# ControlBoardV1.net
KiCad netlist of a schematic drawn in EAGLE
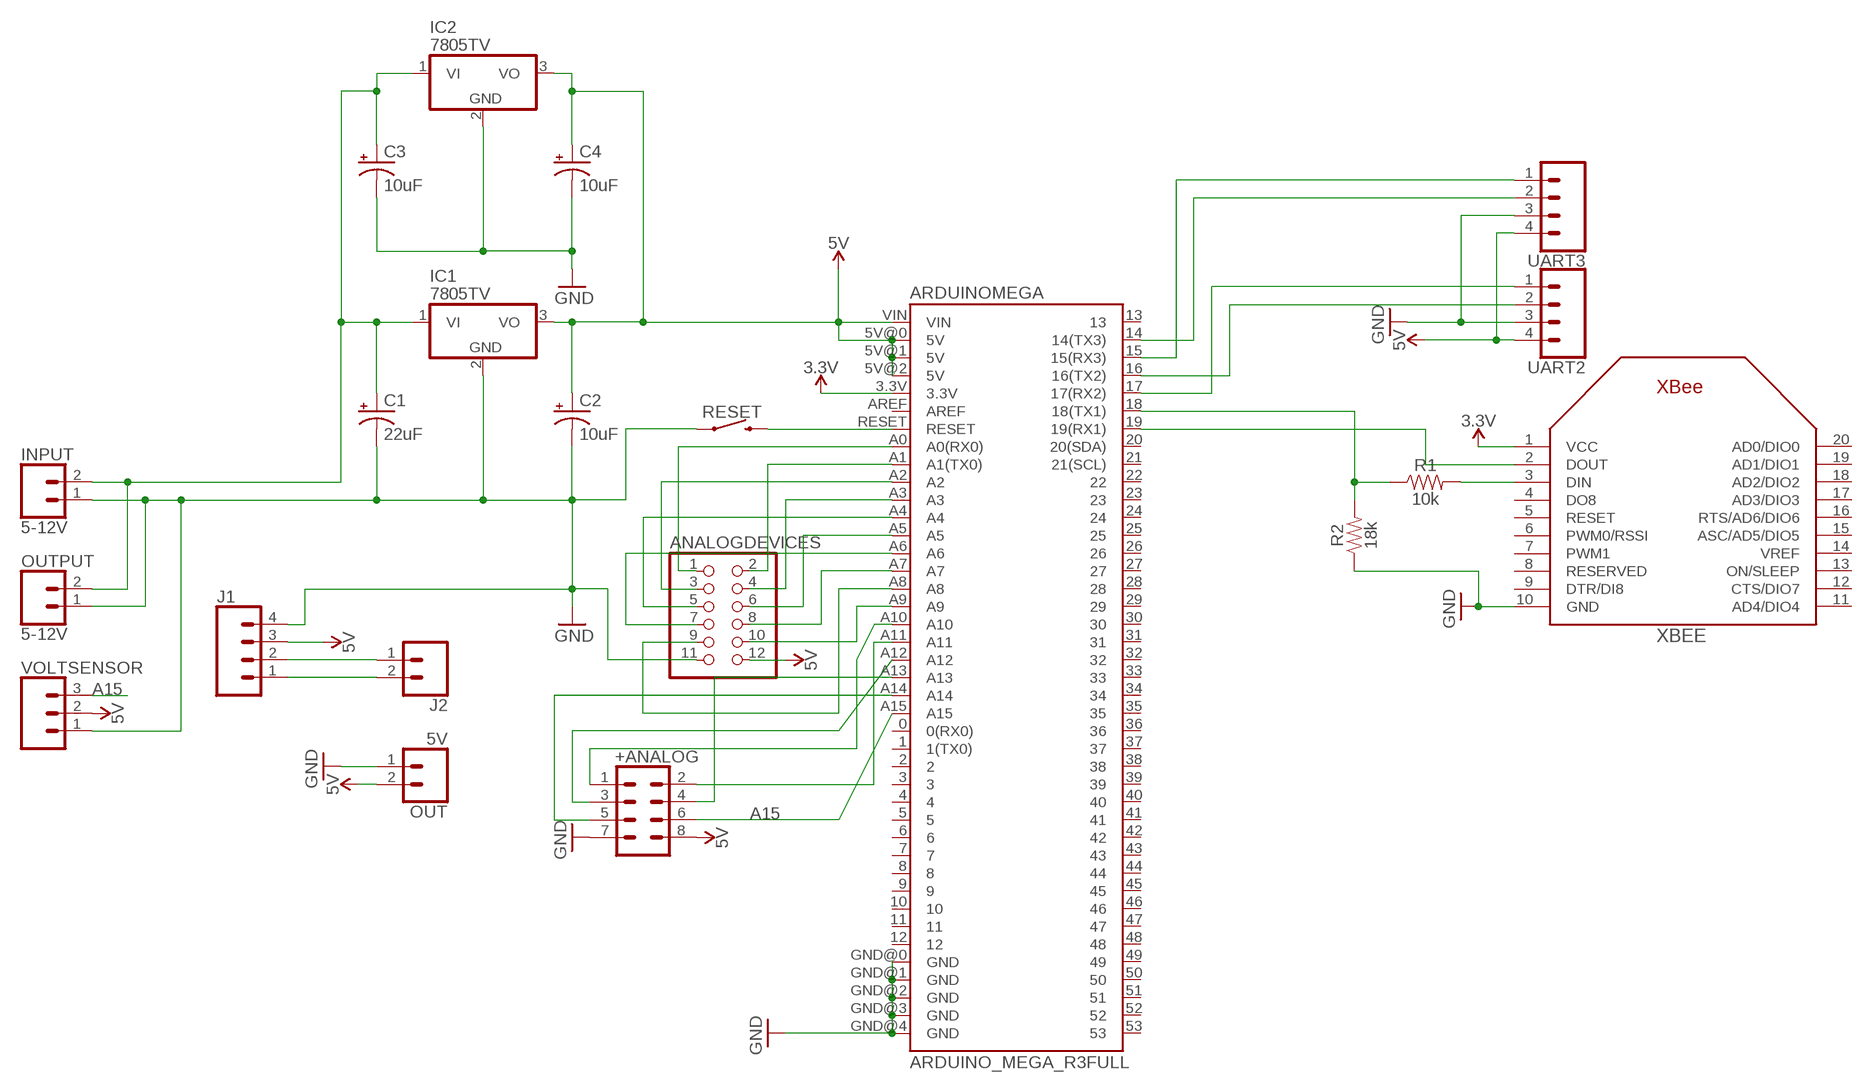
[diagram p0: schematic, sheet 1]

(export (version "E")
  (design (tool "Eeschema 10.0.6"))
  (components
    (comp (ref "+ANALOG")
      (value "CONN_04X2")
      (footprint "eagle-import:2X4")
      (libsource (lib "eagle-import") (part "CONN_04X2"))
    )
    (comp (ref "ANALOGDEVICES")
      (value "PINHD-2X6")
      (footprint "eagle-import:2X06")
      (libsource (lib "eagle-import") (part "PINHD-2X6"))
    )
    (comp (ref "ARDUINOMEGA")
      (value "ARDUINO_MEGA_R3FULL")
      (footprint "eagle-import:ARDUINO_MEGA")
      (libsource (lib "eagle-import") (part "ARDUINO_MEGA_R3FULL"))
    )
    (comp (ref "C1")
      (value "22uF")
      (footprint "eagle-import:E2,5-5")
      (libsource (lib "eagle-import") (part "CPOL-USE2.5-5"))
    )
    (comp (ref "C2")
      (value "10uF")
      (footprint "eagle-import:E2,5-5")
      (libsource (lib "eagle-import") (part "CPOL-USE2.5-5"))
    )
    (comp (ref "C3")
      (value "10uF")
      (footprint "eagle-import:E2,5-5")
      (libsource (lib "eagle-import") (part "CPOL-USE2.5-5"))
    )
    (comp (ref "C4")
      (value "10uF")
      (footprint "eagle-import:E2,5-5")
      (libsource (lib "eagle-import") (part "CPOL-USE2.5-5"))
    )
    (comp (ref "IC1")
      (value "7805TV")
      (footprint "eagle-import:TO220V")
      (libsource (lib "eagle-import") (part "78TV05"))
    )
    (comp (ref "IC2")
      (value "7805TV")
      (footprint "eagle-import:TO220V")
      (libsource (lib "eagle-import") (part "78TV05"))
    )
    (comp (ref "INPUT")
      (value "5-12V")
      (footprint "eagle-import:SCREWTERMINAL-3.5MM-2")
      (libsource (lib "eagle-import") (part "CONN_023.5MM"))
    )
    (comp (ref "J1")
      (value "CONN_04")
      (footprint "eagle-import:1X04")
      (libsource (lib "eagle-import") (part "CONN_04"))
    )
    (comp (ref "J2")
      (value "CONN_02")
      (footprint "eagle-import:1X02")
      (libsource (lib "eagle-import") (part "CONN_02"))
    )
    (comp (ref "OUT")
      (value "5V")
      (footprint "eagle-import:SCREWTERMINAL-3.5MM-2")
      (libsource (lib "eagle-import") (part "CONN_023.5MM"))
    )
    (comp (ref "OUTPUT")
      (value "5-12V")
      (footprint "eagle-import:SCREWTERMINAL-3.5MM-2")
      (libsource (lib "eagle-import") (part "CONN_023.5MM"))
    )
    (comp (ref "R1")
      (value "10k")
      (footprint "eagle-import:AXIAL-0.3")
      (libsource (lib "eagle-import") (part "10KOHM-HORIZ-1/4W-1%"))
    )
    (comp (ref "R2")
      (value "18k")
      (footprint "eagle-import:AXIAL-0.3")
      (libsource (lib "eagle-import") (part "10KOHM-HORIZ-1/4W-1%"))
    )
    (comp (ref "RESET")
      (value "MOMENTARY-SWITCH-SPST-PTH-6.0MM")
      (footprint "eagle-import:TACTILE_SWITCH_PTH_6.0MM")
      (libsource (lib "eagle-import") (part "MOMENTARY-SWITCH-SPST-PTH-6.0MM"))
    )
    (comp (ref "UART2")
      (value "CONN_04")
      (footprint "eagle-import:1X04")
      (libsource (lib "eagle-import") (part "CONN_04"))
    )
    (comp (ref "UART3")
      (value "CONN_04")
      (footprint "eagle-import:1X04")
      (libsource (lib "eagle-import") (part "CONN_04"))
    )
    (comp (ref "VOLTSENSOR")
      (value "CONN_03")
      (footprint "eagle-import:1X03")
      (libsource (lib "eagle-import") (part "CONN_03"))
    )
    (comp (ref "XBEE")
      (value "XBEE")
      (footprint "eagle-import:XBEE")
      (libsource (lib "eagle-import") (part "XBEE"))
    )
  )
  (nets
    (net (code "1") (name "/A15") (class "Default")
      (node (ref "+ANALOG") (pin "6") (pinfunction "6_6") (pintype "passive"))
      (node (ref "ARDUINOMEGA") (pin "A15") (pinfunction "A15_A15") (pintype "bidirectional"))
      (node (ref "VOLTSENSOR") (pin "3") (pinfunction "3_3") (pintype "passive"))
    )
    (net (code "2") (name "3.3V") (class "Default")
      (node (ref "ARDUINOMEGA") (pin "3.3V") (pinfunction "3.3V_3.3V") (pintype "bidirectional"))
      (node (ref "XBEE") (pin "1") (pinfunction "VCC_1") (pintype "power_in"))
    )
    (net (code "3") (name "5V") (class "Default")
      (node (ref "+ANALOG") (pin "8") (pinfunction "8_8") (pintype "passive"))
      (node (ref "ANALOGDEVICES") (pin "12") (pinfunction "12_12") (pintype "passive"))
      (node (ref "ARDUINOMEGA") (pin "5V@0") (pinfunction "5V_5V@0") (pintype "bidirectional"))
      (node (ref "ARDUINOMEGA") (pin "5V@1") (pinfunction "5V_5V@1") (pintype "bidirectional"))
      (node (ref "ARDUINOMEGA") (pin "5V@2") (pinfunction "5V_5V@2") (pintype "bidirectional"))
      (node (ref "ARDUINOMEGA") (pin "VIN") (pinfunction "VIN_VIN") (pintype "bidirectional"))
      (node (ref "C2") (pin "+") (pinfunction "+_+") (pintype "passive"))
      (node (ref "C4") (pin "+") (pinfunction "+_+") (pintype "passive"))
      (node (ref "IC1") (pin "3") (pinfunction "VO_3") (pintype "passive"))
      (node (ref "IC2") (pin "3") (pinfunction "VO_3") (pintype "passive"))
      (node (ref "J1") (pin "3") (pinfunction "3_3") (pintype "passive"))
      (node (ref "OUT") (pin "2") (pinfunction "2_2") (pintype "passive"))
      (node (ref "UART2") (pin "4") (pinfunction "4_4") (pintype "passive"))
      (node (ref "UART3") (pin "4") (pinfunction "4_4") (pintype "passive"))
      (node (ref "VOLTSENSOR") (pin "2") (pinfunction "2_2") (pintype "passive"))
    )
    (net (code "4") (name "GND") (class "Default")
      (node (ref "+ANALOG") (pin "7") (pinfunction "7_7") (pintype "passive"))
      (node (ref "ANALOGDEVICES") (pin "11") (pinfunction "11_11") (pintype "passive"))
      (node (ref "ARDUINOMEGA") (pin "GND@0") (pinfunction "GND_GND@0") (pintype "bidirectional"))
      (node (ref "ARDUINOMEGA") (pin "GND@1") (pinfunction "GND_GND@1") (pintype "bidirectional"))
      (node (ref "ARDUINOMEGA") (pin "GND@2") (pinfunction "GND_GND@2") (pintype "bidirectional"))
      (node (ref "ARDUINOMEGA") (pin "GND@3") (pinfunction "GND_GND@3") (pintype "bidirectional"))
      (node (ref "ARDUINOMEGA") (pin "GND@4") (pinfunction "GND_GND@4") (pintype "bidirectional"))
      (node (ref "C1") (pin "-") (pinfunction "-_-") (pintype "passive"))
      (node (ref "C2") (pin "-") (pinfunction "-_-") (pintype "passive"))
      (node (ref "C3") (pin "-") (pinfunction "-_-") (pintype "passive"))
      (node (ref "C4") (pin "-") (pinfunction "-_-") (pintype "passive"))
      (node (ref "IC1") (pin "2") (pinfunction "GND_2") (pintype "passive"))
      (node (ref "IC2") (pin "2") (pinfunction "GND_2") (pintype "passive"))
      (node (ref "INPUT") (pin "1") (pinfunction "1_1") (pintype "passive"))
      (node (ref "J1") (pin "4") (pinfunction "4_4") (pintype "passive"))
      (node (ref "OUT") (pin "1") (pinfunction "1_1") (pintype "passive"))
      (node (ref "OUTPUT") (pin "1") (pinfunction "1_1") (pintype "passive"))
      (node (ref "R2") (pin "P$1") (pinfunction "1_P$1") (pintype "passive"))
      (node (ref "RESET") (pin "1") (pinfunction "1_1") (pintype "passive"))
      (node (ref "UART2") (pin "3") (pinfunction "3_3") (pintype "passive"))
      (node (ref "UART3") (pin "3") (pinfunction "3_3") (pintype "passive"))
      (node (ref "VOLTSENSOR") (pin "1") (pinfunction "1_1") (pintype "passive"))
      (node (ref "XBEE") (pin "10") (pinfunction "GND_10") (pintype "power_in"))
    )
    (net (code "5") (name "Net-(+ANALOG-Pad1)") (class "Default")
      (node (ref "+ANALOG") (pin "1") (pinfunction "1_1") (pintype "passive"))
      (node (ref "ARDUINOMEGA") (pin "A10") (pinfunction "A10_A10") (pintype "bidirectional"))
    )
    (net (code "6") (name "Net-(+ANALOG-Pad2)") (class "Default")
      (node (ref "+ANALOG") (pin "2") (pinfunction "2_2") (pintype "passive"))
      (node (ref "ARDUINOMEGA") (pin "A11") (pinfunction "A11_A11") (pintype "bidirectional"))
    )
    (net (code "7") (name "Net-(+ANALOG-Pad3)") (class "Default")
      (node (ref "+ANALOG") (pin "3") (pinfunction "3_3") (pintype "passive"))
      (node (ref "ARDUINOMEGA") (pin "A12") (pinfunction "A12_A12") (pintype "bidirectional"))
    )
    (net (code "8") (name "Net-(+ANALOG-Pad4)") (class "Default")
      (node (ref "+ANALOG") (pin "4") (pinfunction "4_4") (pintype "passive"))
      (node (ref "ARDUINOMEGA") (pin "A13") (pinfunction "A13_A13") (pintype "bidirectional"))
    )
    (net (code "9") (name "Net-(+ANALOG-Pad5)") (class "Default")
      (node (ref "+ANALOG") (pin "5") (pinfunction "5_5") (pintype "passive"))
      (node (ref "ARDUINOMEGA") (pin "A14") (pinfunction "A14_A14") (pintype "bidirectional"))
    )
    (net (code "10") (name "Net-(ANALOGDEVICES-Pad3)") (class "Default")
      (node (ref "ANALOGDEVICES") (pin "3") (pinfunction "3_3") (pintype "passive"))
      (node (ref "ARDUINOMEGA") (pin "A2") (pinfunction "A2_A2") (pintype "bidirectional"))
    )
    (net (code "11") (name "Net-(ANALOGDEVICES-Pad4)") (class "Default")
      (node (ref "ANALOGDEVICES") (pin "4") (pinfunction "4_4") (pintype "passive"))
      (node (ref "ARDUINOMEGA") (pin "A3") (pinfunction "A3_A3") (pintype "bidirectional"))
    )
    (net (code "12") (name "Net-(ANALOGDEVICES-Pad5)") (class "Default")
      (node (ref "ANALOGDEVICES") (pin "5") (pinfunction "5_5") (pintype "passive"))
      (node (ref "ARDUINOMEGA") (pin "A4") (pinfunction "A4_A4") (pintype "bidirectional"))
    )
    (net (code "13") (name "Net-(ANALOGDEVICES-Pad6)") (class "Default")
      (node (ref "ANALOGDEVICES") (pin "6") (pinfunction "6_6") (pintype "passive"))
      (node (ref "ARDUINOMEGA") (pin "A5") (pinfunction "A5_A5") (pintype "bidirectional"))
    )
    (net (code "14") (name "Net-(ANALOGDEVICES-Pad7)") (class "Default")
      (node (ref "ANALOGDEVICES") (pin "7") (pinfunction "7_7") (pintype "passive"))
      (node (ref "ARDUINOMEGA") (pin "A6") (pinfunction "A6_A6") (pintype "bidirectional"))
    )
    (net (code "15") (name "Net-(ANALOGDEVICES-Pad8)") (class "Default")
      (node (ref "ANALOGDEVICES") (pin "8") (pinfunction "8_8") (pintype "passive"))
      (node (ref "ARDUINOMEGA") (pin "A7") (pinfunction "A7_A7") (pintype "bidirectional"))
    )
    (net (code "16") (name "Net-(ANALOGDEVICES-Pad9)") (class "Default")
      (node (ref "ANALOGDEVICES") (pin "9") (pinfunction "9_9") (pintype "passive"))
      (node (ref "ARDUINOMEGA") (pin "A8") (pinfunction "A8_A8") (pintype "bidirectional"))
    )
    (net (code "17") (name "Net-(ANALOGDEVICES-Pad10)") (class "Default")
      (node (ref "ANALOGDEVICES") (pin "10") (pinfunction "10_10") (pintype "passive"))
      (node (ref "ARDUINOMEGA") (pin "A9") (pinfunction "A9_A9") (pintype "bidirectional"))
    )
    (net (code "18") (name "Net-(ARDUINOMEGA-14(TX3))") (class "Default")
      (node (ref "ARDUINOMEGA") (pin "14") (pinfunction "14(TX3)_14") (pintype "bidirectional"))
      (node (ref "UART3") (pin "2") (pinfunction "2_2") (pintype "passive"))
    )
    (net (code "19") (name "Net-(ARDUINOMEGA-15(RX3))") (class "Default")
      (node (ref "ARDUINOMEGA") (pin "15") (pinfunction "15(RX3)_15") (pintype "bidirectional"))
      (node (ref "UART3") (pin "1") (pinfunction "1_1") (pintype "passive"))
    )
    (net (code "20") (name "Net-(ARDUINOMEGA-16(TX2))") (class "Default")
      (node (ref "ARDUINOMEGA") (pin "16") (pinfunction "16(TX2)_16") (pintype "bidirectional"))
      (node (ref "UART2") (pin "2") (pinfunction "2_2") (pintype "passive"))
    )
    (net (code "21") (name "Net-(ARDUINOMEGA-17(RX2))") (class "Default")
      (node (ref "ARDUINOMEGA") (pin "17") (pinfunction "17(RX2)_17") (pintype "bidirectional"))
      (node (ref "UART2") (pin "1") (pinfunction "1_1") (pintype "passive"))
    )
    (net (code "22") (name "Net-(ARDUINOMEGA-18(TX1))") (class "Default")
      (node (ref "ARDUINOMEGA") (pin "18") (pinfunction "18(TX1)_18") (pintype "bidirectional"))
      (node (ref "R1") (pin "P$1") (pinfunction "1_P$1") (pintype "passive"))
      (node (ref "R2") (pin "P$2") (pinfunction "2_P$2") (pintype "passive"))
    )
    (net (code "23") (name "Net-(ARDUINOMEGA-19(RX1))") (class "Default")
      (node (ref "ARDUINOMEGA") (pin "19") (pinfunction "19(RX1)_19") (pintype "bidirectional"))
      (node (ref "XBEE") (pin "2") (pinfunction "DOUT_2") (pintype "output"))
    )
    (net (code "24") (name "Net-(ARDUINOMEGA-A0(RX0))") (class "Default")
      (node (ref "ANALOGDEVICES") (pin "1") (pinfunction "1_1") (pintype "passive"))
      (node (ref "ARDUINOMEGA") (pin "A0") (pinfunction "A0(RX0)_A0") (pintype "bidirectional"))
    )
    (net (code "25") (name "Net-(ARDUINOMEGA-A1(TX0))") (class "Default")
      (node (ref "ANALOGDEVICES") (pin "2") (pinfunction "2_2") (pintype "passive"))
      (node (ref "ARDUINOMEGA") (pin "A1") (pinfunction "A1(TX0)_A1") (pintype "bidirectional"))
    )
    (net (code "26") (name "Net-(IC1-VI)") (class "Default")
      (node (ref "C1") (pin "+") (pinfunction "+_+") (pintype "passive"))
      (node (ref "C3") (pin "+") (pinfunction "+_+") (pintype "passive"))
      (node (ref "IC1") (pin "1") (pinfunction "VI_1") (pintype "input"))
      (node (ref "IC2") (pin "1") (pinfunction "VI_1") (pintype "input"))
      (node (ref "INPUT") (pin "2") (pinfunction "2_2") (pintype "passive"))
      (node (ref "OUTPUT") (pin "2") (pinfunction "2_2") (pintype "passive"))
    )
    (net (code "27") (name "Net-(J1-Pad1)") (class "Default")
      (node (ref "J1") (pin "1") (pinfunction "1_1") (pintype "passive"))
      (node (ref "J2") (pin "2") (pinfunction "2_2") (pintype "passive"))
    )
    (net (code "28") (name "Net-(J1-Pad2)") (class "Default")
      (node (ref "J1") (pin "2") (pinfunction "2_2") (pintype "passive"))
      (node (ref "J2") (pin "1") (pinfunction "1_1") (pintype "passive"))
    )
    (net (code "29") (name "Net-(R1-2)") (class "Default")
      (node (ref "R1") (pin "P$2") (pinfunction "2_P$2") (pintype "passive"))
      (node (ref "XBEE") (pin "3") (pinfunction "DIN_3") (pintype "input"))
    )
    (net (code "30") (name "Net-(RESET-2)") (class "Default")
      (node (ref "ARDUINOMEGA") (pin "RESET") (pinfunction "RESET_RESET") (pintype "bidirectional"))
      (node (ref "RESET") (pin "3") (pinfunction "2_3") (pintype "passive"))
    )
    (net (code "31") (name "unconnected-(ARDUINOMEGA-0(RX0)-Pad0)") (class "Default")
      (node (ref "ARDUINOMEGA") (pin "0") (pinfunction "0(RX0)_0") (pintype "bidirectional"))
    )
    (net (code "32") (name "unconnected-(ARDUINOMEGA-1(TX0)-Pad1)") (class "Default")
      (node (ref "ARDUINOMEGA") (pin "1") (pinfunction "1(TX0)_1") (pintype "bidirectional"))
    )
    (net (code "33") (name "unconnected-(ARDUINOMEGA-20(SDA)-Pad20)") (class "Default")
      (node (ref "ARDUINOMEGA") (pin "20") (pinfunction "20(SDA)_20") (pintype "bidirectional"))
    )
    (net (code "34") (name "unconnected-(ARDUINOMEGA-21(SCL)-Pad21)") (class "Default")
      (node (ref "ARDUINOMEGA") (pin "21") (pinfunction "21(SCL)_21") (pintype "bidirectional"))
    )
    (net (code "35") (name "unconnected-(ARDUINOMEGA-Pad2)") (class "Default")
      (node (ref "ARDUINOMEGA") (pin "2") (pinfunction "2_2") (pintype "bidirectional"))
    )
    (net (code "36") (name "unconnected-(ARDUINOMEGA-Pad3)") (class "Default")
      (node (ref "ARDUINOMEGA") (pin "3") (pinfunction "3_3") (pintype "bidirectional"))
    )
    (net (code "37") (name "unconnected-(ARDUINOMEGA-Pad4)") (class "Default")
      (node (ref "ARDUINOMEGA") (pin "4") (pinfunction "4_4") (pintype "bidirectional"))
    )
    (net (code "38") (name "unconnected-(ARDUINOMEGA-Pad5)") (class "Default")
      (node (ref "ARDUINOMEGA") (pin "5") (pinfunction "5_5") (pintype "bidirectional"))
    )
    (net (code "39") (name "unconnected-(ARDUINOMEGA-Pad6)") (class "Default")
      (node (ref "ARDUINOMEGA") (pin "6") (pinfunction "6_6") (pintype "bidirectional"))
    )
    (net (code "40") (name "unconnected-(ARDUINOMEGA-Pad7)") (class "Default")
      (node (ref "ARDUINOMEGA") (pin "7") (pinfunction "7_7") (pintype "bidirectional"))
    )
    (net (code "41") (name "unconnected-(ARDUINOMEGA-Pad8)") (class "Default")
      (node (ref "ARDUINOMEGA") (pin "8") (pinfunction "8_8") (pintype "bidirectional"))
    )
    (net (code "42") (name "unconnected-(ARDUINOMEGA-Pad9)") (class "Default")
      (node (ref "ARDUINOMEGA") (pin "9") (pinfunction "9_9") (pintype "bidirectional"))
    )
    (net (code "43") (name "unconnected-(ARDUINOMEGA-Pad10)") (class "Default")
      (node (ref "ARDUINOMEGA") (pin "10") (pinfunction "10_10") (pintype "bidirectional"))
    )
    (net (code "44") (name "unconnected-(ARDUINOMEGA-Pad11)") (class "Default")
      (node (ref "ARDUINOMEGA") (pin "11") (pinfunction "11_11") (pintype "bidirectional"))
    )
    (net (code "45") (name "unconnected-(ARDUINOMEGA-Pad12)") (class "Default")
      (node (ref "ARDUINOMEGA") (pin "12") (pinfunction "12_12") (pintype "bidirectional"))
    )
    (net (code "46") (name "unconnected-(ARDUINOMEGA-Pad13)") (class "Default")
      (node (ref "ARDUINOMEGA") (pin "13") (pinfunction "13_13") (pintype "bidirectional"))
    )
    (net (code "47") (name "unconnected-(ARDUINOMEGA-Pad22)") (class "Default")
      (node (ref "ARDUINOMEGA") (pin "22") (pinfunction "22_22") (pintype "bidirectional"))
    )
    (net (code "48") (name "unconnected-(ARDUINOMEGA-Pad23)") (class "Default")
      (node (ref "ARDUINOMEGA") (pin "23") (pinfunction "23_23") (pintype "bidirectional"))
    )
    (net (code "49") (name "unconnected-(ARDUINOMEGA-Pad24)") (class "Default")
      (node (ref "ARDUINOMEGA") (pin "24") (pinfunction "24_24") (pintype "bidirectional"))
    )
    (net (code "50") (name "unconnected-(ARDUINOMEGA-Pad25)") (class "Default")
      (node (ref "ARDUINOMEGA") (pin "25") (pinfunction "25_25") (pintype "bidirectional"))
    )
    (net (code "51") (name "unconnected-(ARDUINOMEGA-Pad26)") (class "Default")
      (node (ref "ARDUINOMEGA") (pin "26") (pinfunction "26_26") (pintype "bidirectional"))
    )
    (net (code "52") (name "unconnected-(ARDUINOMEGA-Pad27)") (class "Default")
      (node (ref "ARDUINOMEGA") (pin "27") (pinfunction "27_27") (pintype "bidirectional"))
    )
    (net (code "53") (name "unconnected-(ARDUINOMEGA-Pad28)") (class "Default")
      (node (ref "ARDUINOMEGA") (pin "28") (pinfunction "28_28") (pintype "bidirectional"))
    )
    (net (code "54") (name "unconnected-(ARDUINOMEGA-Pad29)") (class "Default")
      (node (ref "ARDUINOMEGA") (pin "29") (pinfunction "29_29") (pintype "bidirectional"))
    )
    (net (code "55") (name "unconnected-(ARDUINOMEGA-Pad30)") (class "Default")
      (node (ref "ARDUINOMEGA") (pin "30") (pinfunction "30_30") (pintype "bidirectional"))
    )
    (net (code "56") (name "unconnected-(ARDUINOMEGA-Pad31)") (class "Default")
      (node (ref "ARDUINOMEGA") (pin "31") (pinfunction "31_31") (pintype "bidirectional"))
    )
    (net (code "57") (name "unconnected-(ARDUINOMEGA-Pad32)") (class "Default")
      (node (ref "ARDUINOMEGA") (pin "32") (pinfunction "32_32") (pintype "bidirectional"))
    )
    (net (code "58") (name "unconnected-(ARDUINOMEGA-Pad33)") (class "Default")
      (node (ref "ARDUINOMEGA") (pin "33") (pinfunction "33_33") (pintype "bidirectional"))
    )
    (net (code "59") (name "unconnected-(ARDUINOMEGA-Pad34)") (class "Default")
      (node (ref "ARDUINOMEGA") (pin "34") (pinfunction "34_34") (pintype "bidirectional"))
    )
    (net (code "60") (name "unconnected-(ARDUINOMEGA-Pad35)") (class "Default")
      (node (ref "ARDUINOMEGA") (pin "35") (pinfunction "35_35") (pintype "bidirectional"))
    )
    (net (code "61") (name "unconnected-(ARDUINOMEGA-Pad36)") (class "Default")
      (node (ref "ARDUINOMEGA") (pin "36") (pinfunction "36_36") (pintype "bidirectional"))
    )
    (net (code "62") (name "unconnected-(ARDUINOMEGA-Pad37)") (class "Default")
      (node (ref "ARDUINOMEGA") (pin "37") (pinfunction "37_37") (pintype "bidirectional"))
    )
    (net (code "63") (name "unconnected-(ARDUINOMEGA-Pad38)") (class "Default")
      (node (ref "ARDUINOMEGA") (pin "38") (pinfunction "38_38") (pintype "bidirectional"))
    )
    (net (code "64") (name "unconnected-(ARDUINOMEGA-Pad39)") (class "Default")
      (node (ref "ARDUINOMEGA") (pin "39") (pinfunction "39_39") (pintype "bidirectional"))
    )
    (net (code "65") (name "unconnected-(ARDUINOMEGA-Pad40)") (class "Default")
      (node (ref "ARDUINOMEGA") (pin "40") (pinfunction "40_40") (pintype "bidirectional"))
    )
    (net (code "66") (name "unconnected-(ARDUINOMEGA-Pad41)") (class "Default")
      (node (ref "ARDUINOMEGA") (pin "41") (pinfunction "41_41") (pintype "bidirectional"))
    )
    (net (code "67") (name "unconnected-(ARDUINOMEGA-Pad42)") (class "Default")
      (node (ref "ARDUINOMEGA") (pin "42") (pinfunction "42_42") (pintype "bidirectional"))
    )
    (net (code "68") (name "unconnected-(ARDUINOMEGA-Pad43)") (class "Default")
      (node (ref "ARDUINOMEGA") (pin "43") (pinfunction "43_43") (pintype "bidirectional"))
    )
    (net (code "69") (name "unconnected-(ARDUINOMEGA-Pad44)") (class "Default")
      (node (ref "ARDUINOMEGA") (pin "44") (pinfunction "44_44") (pintype "bidirectional"))
    )
    (net (code "70") (name "unconnected-(ARDUINOMEGA-Pad45)") (class "Default")
      (node (ref "ARDUINOMEGA") (pin "45") (pinfunction "45_45") (pintype "bidirectional"))
    )
    (net (code "71") (name "unconnected-(ARDUINOMEGA-Pad46)") (class "Default")
      (node (ref "ARDUINOMEGA") (pin "46") (pinfunction "46_46") (pintype "bidirectional"))
    )
    (net (code "72") (name "unconnected-(ARDUINOMEGA-Pad47)") (class "Default")
      (node (ref "ARDUINOMEGA") (pin "47") (pinfunction "47_47") (pintype "bidirectional"))
    )
    (net (code "73") (name "unconnected-(ARDUINOMEGA-Pad48)") (class "Default")
      (node (ref "ARDUINOMEGA") (pin "48") (pinfunction "48_48") (pintype "bidirectional"))
    )
    (net (code "74") (name "unconnected-(ARDUINOMEGA-Pad49)") (class "Default")
      (node (ref "ARDUINOMEGA") (pin "49") (pinfunction "49_49") (pintype "bidirectional"))
    )
    (net (code "75") (name "unconnected-(ARDUINOMEGA-Pad50)") (class "Default")
      (node (ref "ARDUINOMEGA") (pin "50") (pinfunction "50_50") (pintype "bidirectional"))
    )
    (net (code "76") (name "unconnected-(ARDUINOMEGA-Pad51)") (class "Default")
      (node (ref "ARDUINOMEGA") (pin "51") (pinfunction "51_51") (pintype "bidirectional"))
    )
    (net (code "77") (name "unconnected-(ARDUINOMEGA-Pad52)") (class "Default")
      (node (ref "ARDUINOMEGA") (pin "52") (pinfunction "52_52") (pintype "bidirectional"))
    )
    (net (code "78") (name "unconnected-(ARDUINOMEGA-Pad53)") (class "Default")
      (node (ref "ARDUINOMEGA") (pin "53") (pinfunction "53_53") (pintype "bidirectional"))
    )
    (net (code "79") (name "unconnected-(ARDUINOMEGA-PadAREF)") (class "Default")
      (node (ref "ARDUINOMEGA") (pin "AREF") (pinfunction "AREF_AREF") (pintype "bidirectional"))
    )
    (net (code "80") (name "unconnected-(XBEE-AD0{slash}DIO0-Pad20)") (class "Default")
      (node (ref "XBEE") (pin "20") (pinfunction "AD0/DIO0_20") (pintype "bidirectional"))
    )
    (net (code "81") (name "unconnected-(XBEE-AD1{slash}DIO1-Pad19)") (class "Default")
      (node (ref "XBEE") (pin "19") (pinfunction "AD1/DIO1_19") (pintype "bidirectional"))
    )
    (net (code "82") (name "unconnected-(XBEE-AD2{slash}DIO2-Pad18)") (class "Default")
      (node (ref "XBEE") (pin "18") (pinfunction "AD2/DIO2_18") (pintype "bidirectional"))
    )
    (net (code "83") (name "unconnected-(XBEE-AD3{slash}DIO3-Pad17)") (class "Default")
      (node (ref "XBEE") (pin "17") (pinfunction "AD3/DIO3_17") (pintype "bidirectional"))
    )
    (net (code "84") (name "unconnected-(XBEE-AD4{slash}DIO4-Pad11)") (class "Default")
      (node (ref "XBEE") (pin "11") (pinfunction "AD4/DIO4_11") (pintype "bidirectional"))
    )
    (net (code "85") (name "unconnected-(XBEE-ASC{slash}AD5{slash}DIO5-Pad15)") (class "Default")
      (node (ref "XBEE") (pin "15") (pinfunction "ASC/AD5/DIO5_15") (pintype "bidirectional"))
    )
    (net (code "86") (name "unconnected-(XBEE-CTS{slash}DIO7-Pad12)") (class "Default")
      (node (ref "XBEE") (pin "12") (pinfunction "CTS/DIO7_12") (pintype "bidirectional"))
    )
    (net (code "87") (name "unconnected-(XBEE-DO8-Pad4)") (class "Default")
      (node (ref "XBEE") (pin "4") (pinfunction "DO8_4") (pintype "output"))
    )
    (net (code "88") (name "unconnected-(XBEE-DTR{slash}DI8-Pad9)") (class "Default")
      (node (ref "XBEE") (pin "9") (pinfunction "DTR/DI8_9") (pintype "input"))
    )
    (net (code "89") (name "unconnected-(XBEE-ON{slash}SLEEP-Pad13)") (class "Default")
      (node (ref "XBEE") (pin "13") (pinfunction "ON/SLEEP_13") (pintype "output"))
    )
    (net (code "90") (name "unconnected-(XBEE-PWM0{slash}RSSI-Pad6)") (class "Default")
      (node (ref "XBEE") (pin "6") (pinfunction "PWM0/RSSI_6") (pintype "output"))
    )
    (net (code "91") (name "unconnected-(XBEE-PWM1-Pad7)") (class "Default")
      (node (ref "XBEE") (pin "7") (pinfunction "PWM1_7") (pintype "output"))
    )
    (net (code "92") (name "unconnected-(XBEE-RESERVED-Pad8)") (class "Default")
      (node (ref "XBEE") (pin "8") (pinfunction "RESERVED_8") (pintype "no_connect"))
    )
    (net (code "93") (name "unconnected-(XBEE-RESET-Pad5)") (class "Default")
      (node (ref "XBEE") (pin "5") (pinfunction "RESET_5") (pintype "input"))
    )
    (net (code "94") (name "unconnected-(XBEE-RTS{slash}AD6{slash}DIO6-Pad16)") (class "Default")
      (node (ref "XBEE") (pin "16") (pinfunction "RTS/AD6/DIO6_16") (pintype "bidirectional"))
    )
    (net (code "95") (name "unconnected-(XBEE-VREF-Pad14)") (class "Default")
      (node (ref "XBEE") (pin "14") (pinfunction "VREF_14") (pintype "input"))
    )
  )
)
